# ESP8266_MySensorsGateway_v1_2.net
KiCad netlist of a schematic drawn in EAGLE
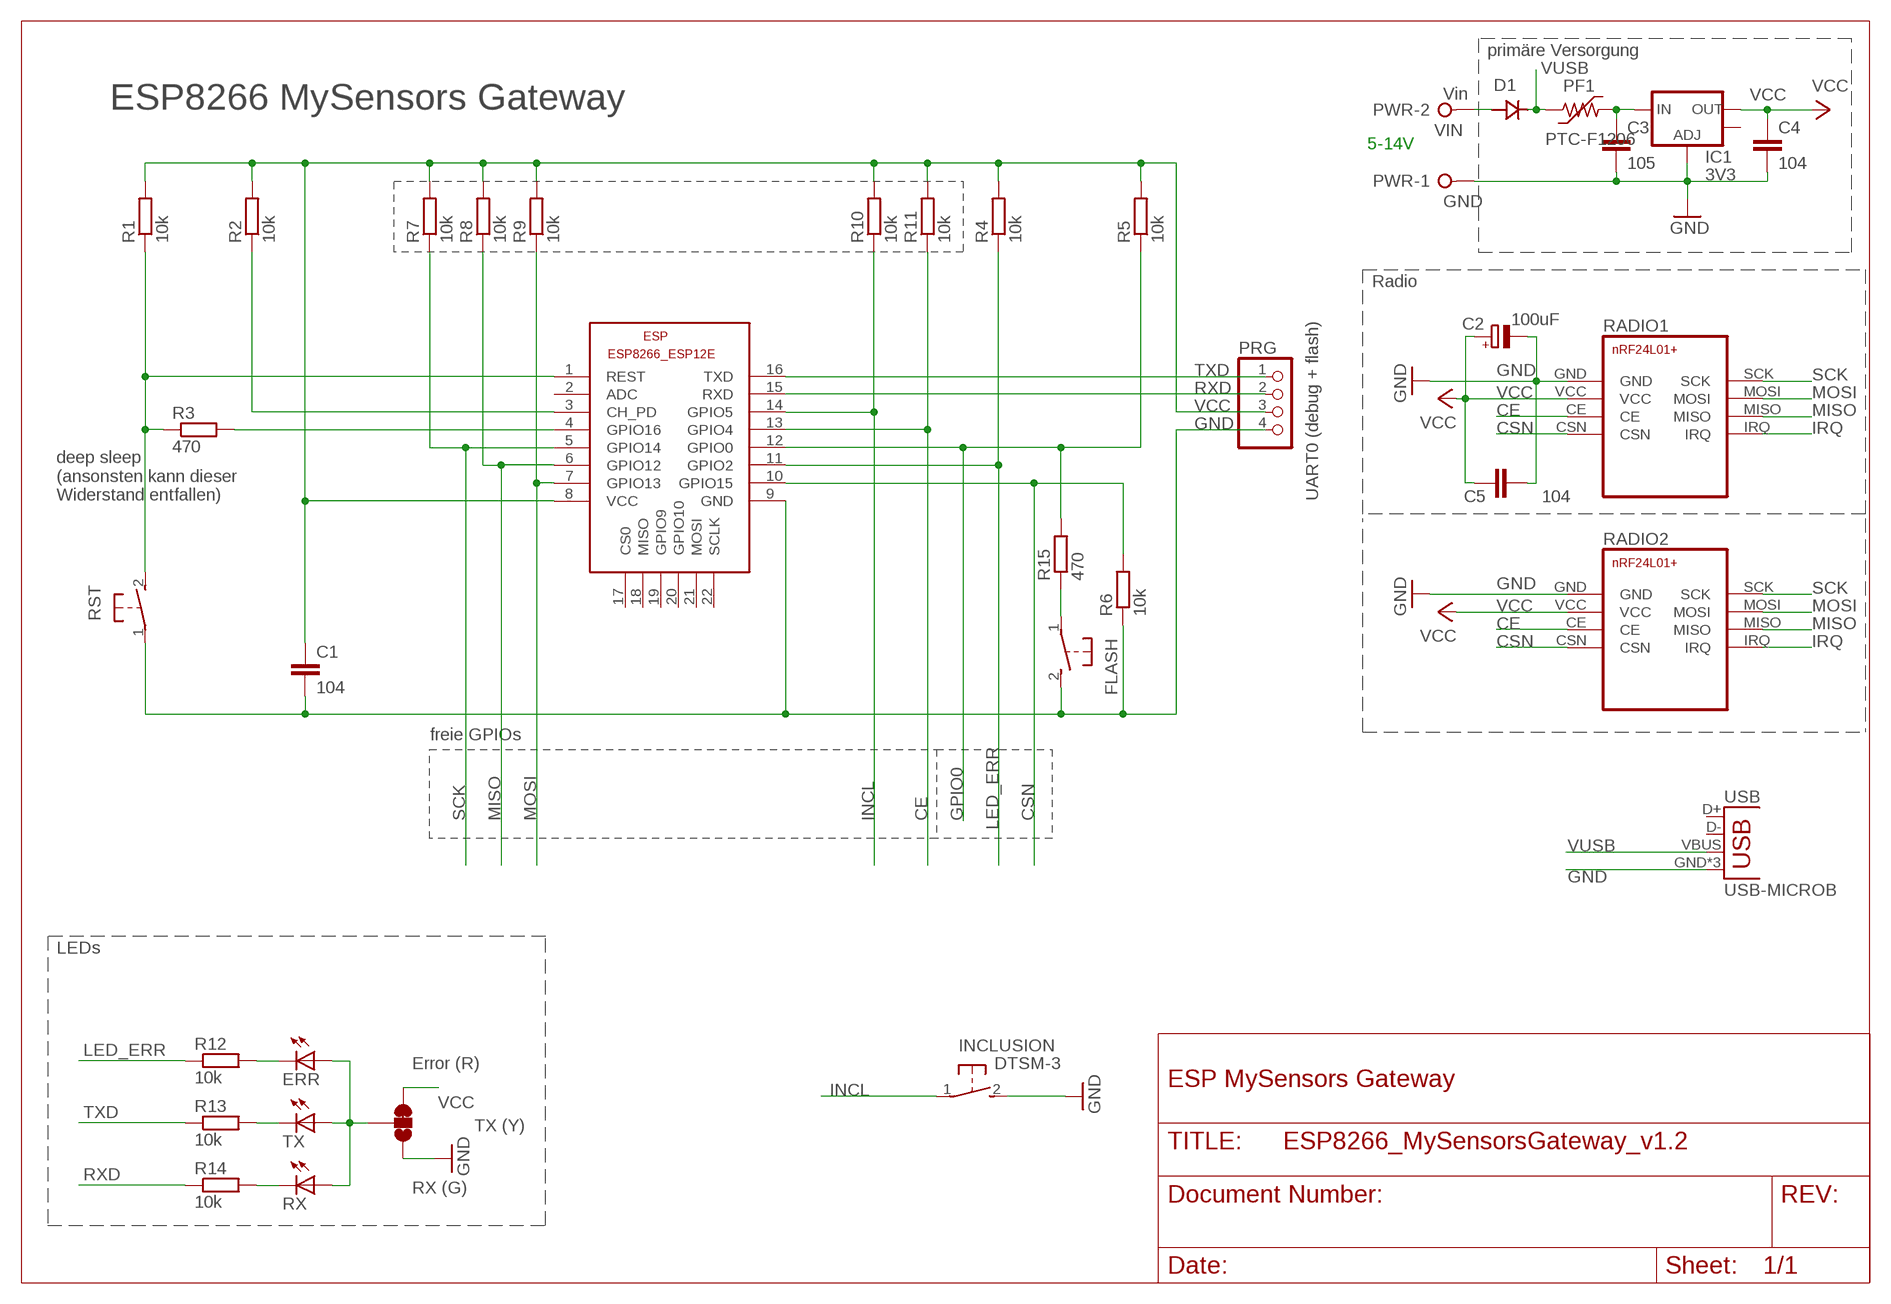
[diagram p0: schematic, sheet 1]

(export (version "E")
  (design (tool "Eeschema 10.0.6"))
  (components
    (comp (ref "C1")
      (value "104")
      (footprint "eagle-import:C0805")
      (libsource (lib "eagle-import") (part "C-EUC0805"))
    )
    (comp (ref "C2")
      (value "100uF")
      (footprint "eagle-import:E2,5-6E")
      (libsource (lib "eagle-import") (part "CPOL-EUE2,5-6E"))
    )
    (comp (ref "C3")
      (value "105")
      (footprint "eagle-import:C0805")
      (libsource (lib "eagle-import") (part "C-EUC0805"))
    )
    (comp (ref "C4")
      (value "104")
      (footprint "eagle-import:C0805")
      (libsource (lib "eagle-import") (part "C-EUC0805"))
    )
    (comp (ref "C5")
      (value "104")
      (footprint "eagle-import:C0805")
      (libsource (lib "eagle-import") (part "C-EUC0805"))
    )
    (comp (ref "D1")
      (value "SS14")
      (footprint "eagle-import:DO214")
      (libsource (lib "eagle-import") (part "SS14"))
    )
    (comp (ref "ERR")
      (value "R")
      (footprint "eagle-import:CHIPLED_1206")
      (libsource (lib "eagle-import") (part "LEDCHIPLED_1206"))
    )
    (comp (ref "ESP")
      (value "µC")
      (footprint "eagle-import:ESP8266-ESP12E")
      (libsource (lib "eagle-import") (part "ESP8266-12EESP8266-ESP12E"))
    )
    (comp (ref "FLASH")
      (value "DTSM-3")
      (footprint "eagle-import:DTSM-3")
      (libsource (lib "eagle-import") (part "DTSM-3"))
    )
    (comp (ref "IC1")
      (value "3V3")
      (footprint "eagle-import:SOT223")
      (libsource (lib "eagle-import") (part "V_REG_LM1117SOT223"))
    )
    (comp (ref "INCLUSION")
      (value "DTSM-3")
      (footprint "eagle-import:DTSM-3")
      (libsource (lib "eagle-import") (part "DTSM-3"))
    )
    (comp (ref "PF1")
      (value "PTC-F1206")
      (footprint "eagle-import:F1206")
      (libsource (lib "eagle-import") (part "PTC-F1206"))
    )
    (comp (ref "PRG")
      (value "PINHD-1X4_S")
      (footprint "eagle-import:1X04")
      (libsource (lib "eagle-import") (part "PINHD-1X4_S"))
    )
    (comp (ref "PWR")
      (value "Vin")
      (footprint "eagle-import:W237-132")
      (libsource (lib "eagle-import") (part "W237-02P"))
    )
    (comp (ref "R1")
      (value "10k")
      (footprint "eagle-import:R0805")
      (libsource (lib "eagle-import") (part "resistor_R-EU_R0805"))
    )
    (comp (ref "R2")
      (value "10k")
      (footprint "eagle-import:R0805")
      (libsource (lib "eagle-import") (part "resistor_R-EU_R0805"))
    )
    (comp (ref "R3")
      (value "470")
      (footprint "eagle-import:R0805")
      (libsource (lib "eagle-import") (part "resistor_R-EU_R0805"))
    )
    (comp (ref "R4")
      (value "10k")
      (footprint "eagle-import:R0805")
      (libsource (lib "eagle-import") (part "resistor_R-EU_R0805"))
    )
    (comp (ref "R5")
      (value "10k")
      (footprint "eagle-import:R0805")
      (libsource (lib "eagle-import") (part "resistor_R-EU_R0805"))
    )
    (comp (ref "R6")
      (value "10k")
      (footprint "eagle-import:R0805")
      (libsource (lib "eagle-import") (part "resistor_R-EU_R0805"))
    )
    (comp (ref "R7")
      (value "10k")
      (footprint "eagle-import:R0805")
      (libsource (lib "eagle-import") (part "resistor_R-EU_R0805"))
    )
    (comp (ref "R8")
      (value "10k")
      (footprint "eagle-import:R0805")
      (libsource (lib "eagle-import") (part "resistor_R-EU_R0805"))
    )
    (comp (ref "R9")
      (value "10k")
      (footprint "eagle-import:R0805")
      (libsource (lib "eagle-import") (part "resistor_R-EU_R0805"))
    )
    (comp (ref "R10")
      (value "10k")
      (footprint "eagle-import:R0805")
      (libsource (lib "eagle-import") (part "resistor_R-EU_R0805"))
    )
    (comp (ref "R11")
      (value "10k")
      (footprint "eagle-import:R0805")
      (libsource (lib "eagle-import") (part "resistor_R-EU_R0805"))
    )
    (comp (ref "R12")
      (value "10k")
      (footprint "eagle-import:R0805")
      (libsource (lib "eagle-import") (part "R-EU_R0805"))
    )
    (comp (ref "R13")
      (value "10k")
      (footprint "eagle-import:R0805")
      (libsource (lib "eagle-import") (part "R-EU_R0805"))
    )
    (comp (ref "R14")
      (value "10k")
      (footprint "eagle-import:R0805")
      (libsource (lib "eagle-import") (part "R-EU_R0805"))
    )
    (comp (ref "R15")
      (value "470")
      (footprint "eagle-import:R0805")
      (libsource (lib "eagle-import") (part "resistor_R-EU_R0805"))
    )
    (comp (ref "RADIO1")
      (value "NRF24L01+")
      (footprint "eagle-import:NRF24L01+")
      (libsource (lib "eagle-import") (part "NRF24L01+"))
    )
    (comp (ref "RADIO2")
      (value "NRF24L01+NRF24L01+MINI")
      (footprint "eagle-import:NRF24L01+MINI")
      (libsource (lib "eagle-import") (part "NRF24L01+NRF24L01+MINI"))
    )
    (comp (ref "RST")
      (value "DTSM-3")
      (footprint "eagle-import:DTSM-3")
      (libsource (lib "eagle-import") (part "DTSM-3"))
    )
    (comp (ref "RX")
      (value "G")
      (footprint "eagle-import:CHIPLED_1206")
      (libsource (lib "eagle-import") (part "LEDCHIPLED_1206"))
    )
    (comp (ref "SJ1")
      (value "JUMPER-PAD-3-2OF3_NC_BY_TRACE_SMALL")
      (footprint "eagle-import:PAD-JUMPER-3-2OF3_NC_BY_TRACE_YES_SILK_FULL_BOX")
      (libsource (lib "eagle-import") (part "JUMPER-PAD-3-2OF3_NC_BY_TRACE_SMALL"))
    )
    (comp (ref "TX")
      (value "Y")
      (footprint "eagle-import:CHIPLED_1206")
      (libsource (lib "eagle-import") (part "LEDCHIPLED_1206"))
    )
    (comp (ref "USB")
      (value "USB-MICROB")
      (footprint "eagle-import:USB-MICROB")
      (libsource (lib "eagle-import") (part "USB-MICROB"))
    )
  )
  (nets
    (net (code "1") (name "/CE") (class "Default")
      (node (ref "ESP") (pin "13") (pinfunction "GPIO4_13") (pintype "bidirectional"))
      (node (ref "R11") (pin "1") (pinfunction "1_1") (pintype "passive"))
      (node (ref "RADIO1") (pin "CE") (pinfunction "CE_CE") (pintype "bidirectional"))
      (node (ref "RADIO2") (pin "CE") (pinfunction "CE_CE") (pintype "bidirectional"))
    )
    (net (code "2") (name "/CSN") (class "Default")
      (node (ref "ESP") (pin "10") (pinfunction "GPIO15_10") (pintype "bidirectional"))
      (node (ref "R6") (pin "2") (pinfunction "2_2") (pintype "passive"))
      (node (ref "RADIO1") (pin "CSN") (pinfunction "CSN_CSN") (pintype "bidirectional"))
      (node (ref "RADIO2") (pin "CSN") (pinfunction "CSN_CSN") (pintype "bidirectional"))
    )
    (net (code "3") (name "/GPIO0") (class "Default")
      (node (ref "ESP") (pin "12") (pinfunction "GPIO0_12") (pintype "bidirectional"))
      (node (ref "R15") (pin "2") (pinfunction "2_2") (pintype "passive"))
      (node (ref "R5") (pin "1") (pinfunction "1_1") (pintype "passive"))
    )
    (net (code "4") (name "/INCL") (class "Default")
      (node (ref "ESP") (pin "14") (pinfunction "GPIO5_14") (pintype "bidirectional"))
      (node (ref "INCLUSION") (pin "1") (pinfunction "1_1") (pintype "passive"))
      (node (ref "R10") (pin "1") (pinfunction "1_1") (pintype "passive"))
    )
    (net (code "5") (name "/IRQ") (class "Default")
      (node (ref "RADIO1") (pin "IRQ") (pinfunction "IRQ_IRQ") (pintype "bidirectional"))
      (node (ref "RADIO2") (pin "IRQ") (pinfunction "IRQ_IRQ") (pintype "bidirectional"))
    )
    (net (code "6") (name "/LED_ERR") (class "Default")
      (node (ref "ESP") (pin "11") (pinfunction "GPIO2_11") (pintype "bidirectional"))
      (node (ref "R12") (pin "1") (pinfunction "1_1") (pintype "passive"))
      (node (ref "R4") (pin "1") (pinfunction "1_1") (pintype "passive"))
    )
    (net (code "7") (name "/MISO") (class "Default")
      (node (ref "ESP") (pin "6") (pinfunction "GPIO12_6") (pintype "bidirectional"))
      (node (ref "R8") (pin "1") (pinfunction "1_1") (pintype "passive"))
      (node (ref "RADIO1") (pin "MISO") (pinfunction "MISO_MISO") (pintype "bidirectional"))
      (node (ref "RADIO2") (pin "MISO") (pinfunction "MISO_MISO") (pintype "bidirectional"))
    )
    (net (code "8") (name "/MOSI") (class "Default")
      (node (ref "ESP") (pin "7") (pinfunction "GPIO13_7") (pintype "bidirectional"))
      (node (ref "R9") (pin "1") (pinfunction "1_1") (pintype "passive"))
      (node (ref "RADIO1") (pin "MOSI") (pinfunction "MOSI_MOSI") (pintype "bidirectional"))
      (node (ref "RADIO2") (pin "MOSI") (pinfunction "MOSI_MOSI") (pintype "bidirectional"))
    )
    (net (code "9") (name "/RXD") (class "Default")
      (node (ref "ESP") (pin "15") (pinfunction "RXD_15") (pintype "bidirectional"))
      (node (ref "PRG") (pin "2") (pinfunction "2_2") (pintype "passive"))
      (node (ref "R14") (pin "1") (pinfunction "1_1") (pintype "passive"))
    )
    (net (code "10") (name "/SCK") (class "Default")
      (node (ref "ESP") (pin "5") (pinfunction "GPIO14_5") (pintype "bidirectional"))
      (node (ref "R7") (pin "1") (pinfunction "1_1") (pintype "passive"))
      (node (ref "RADIO1") (pin "SCK") (pinfunction "SCK_SCK") (pintype "bidirectional"))
      (node (ref "RADIO2") (pin "SCK") (pinfunction "SCK_SCK") (pintype "bidirectional"))
    )
    (net (code "11") (name "/TXD") (class "Default")
      (node (ref "ESP") (pin "16") (pinfunction "TXD_16") (pintype "bidirectional"))
      (node (ref "PRG") (pin "1") (pinfunction "1_1") (pintype "passive"))
      (node (ref "R13") (pin "1") (pinfunction "1_1") (pintype "passive"))
    )
    (net (code "12") (name "/VIN") (class "Default")
      (node (ref "D1") (pin "ANODE") (pinfunction "ANODE_ANODE") (pintype "bidirectional"))
      (node (ref "PWR") (pin "2") (pinfunction "KL_2") (pintype "passive"))
    )
    (net (code "13") (name "/VUSB") (class "Default")
      (node (ref "D1") (pin "CATHODE") (pinfunction "CATHODE_CATHODE") (pintype "bidirectional"))
      (node (ref "PF1") (pin "1") (pinfunction "1_1") (pintype "passive"))
      (node (ref "USB") (pin "VBUS") (pinfunction "VBUS_VBUS") (pintype "bidirectional"))
    )
    (net (code "14") (name "GND") (class "Default")
      (node (ref "C1") (pin "2") (pinfunction "2_2") (pintype "passive"))
      (node (ref "C2") (pin "-") (pinfunction "-_-") (pintype "passive"))
      (node (ref "C3") (pin "2") (pinfunction "2_2") (pintype "passive"))
      (node (ref "C4") (pin "2") (pinfunction "2_2") (pintype "passive"))
      (node (ref "C5") (pin "2") (pinfunction "2_2") (pintype "passive"))
      (node (ref "ESP") (pin "9") (pinfunction "GND_9") (pintype "bidirectional"))
      (node (ref "FLASH") (pin "2") (pinfunction "2_2") (pintype "passive"))
      (node (ref "IC1") (pin "1") (pinfunction "ADJ_1") (pintype "input"))
      (node (ref "INCLUSION") (pin "2") (pinfunction "2_2") (pintype "passive"))
      (node (ref "PRG") (pin "4") (pinfunction "4_4") (pintype "passive"))
      (node (ref "PWR") (pin "1") (pinfunction "KL_1") (pintype "passive"))
      (node (ref "R6") (pin "1") (pinfunction "1_1") (pintype "passive"))
      (node (ref "RADIO1") (pin "GND") (pinfunction "GND_GND") (pintype "power_in"))
      (node (ref "RADIO2") (pin "GND") (pinfunction "GND_GND") (pintype "power_in"))
      (node (ref "RST") (pin "1") (pinfunction "1_1") (pintype "passive"))
      (node (ref "SJ1") (pin "1") (pinfunction "1_1") (pintype "passive"))
      (node (ref "USB") (pin "GND") (pinfunction "GND_GND") (pintype "bidirectional"))
      (node (ref "USB") (pin "MT1") (pinfunction "GND_MT1") (pintype "bidirectional"))
      (node (ref "USB") (pin "MT2") (pinfunction "GND_MT2") (pintype "bidirectional"))
    )
    (net (code "15") (name "Net-(ERR-PadA)") (class "Default")
      (node (ref "ERR") (pin "A") (pinfunction "A_A") (pintype "passive"))
      (node (ref "RX") (pin "A") (pinfunction "A_A") (pintype "passive"))
      (node (ref "SJ1") (pin "2") (pinfunction "2_2") (pintype "passive"))
      (node (ref "TX") (pin "A") (pinfunction "A_A") (pintype "passive"))
    )
    (net (code "16") (name "Net-(ERR-PadC)") (class "Default")
      (node (ref "ERR") (pin "C") (pinfunction "C_C") (pintype "passive"))
      (node (ref "R12") (pin "2") (pinfunction "2_2") (pintype "passive"))
    )
    (net (code "17") (name "Net-(ESP-CH_PD)") (class "Default")
      (node (ref "ESP") (pin "3") (pinfunction "CH_PD_3") (pintype "bidirectional"))
      (node (ref "R2") (pin "1") (pinfunction "1_1") (pintype "passive"))
    )
    (net (code "18") (name "Net-(ESP-GPIO16)") (class "Default")
      (node (ref "ESP") (pin "4") (pinfunction "GPIO16_4") (pintype "bidirectional"))
      (node (ref "R3") (pin "2") (pinfunction "2_2") (pintype "passive"))
    )
    (net (code "19") (name "Net-(ESP-REST)") (class "Default")
      (node (ref "ESP") (pin "1") (pinfunction "REST_1") (pintype "bidirectional"))
      (node (ref "R1") (pin "1") (pinfunction "1_1") (pintype "passive"))
      (node (ref "R3") (pin "1") (pinfunction "1_1") (pintype "passive"))
      (node (ref "RST") (pin "2") (pinfunction "2_2") (pintype "passive"))
    )
    (net (code "20") (name "Net-(FLASH-Pad1)") (class "Default")
      (node (ref "FLASH") (pin "1") (pinfunction "1_1") (pintype "passive"))
      (node (ref "R15") (pin "1") (pinfunction "1_1") (pintype "passive"))
    )
    (net (code "21") (name "Net-(IC1-IN)") (class "Default")
      (node (ref "C3") (pin "1") (pinfunction "1_1") (pintype "passive"))
      (node (ref "IC1") (pin "3") (pinfunction "IN_3") (pintype "input"))
      (node (ref "PF1") (pin "2") (pinfunction "2_2") (pintype "passive"))
    )
    (net (code "22") (name "Net-(R13-Pad2)") (class "Default")
      (node (ref "R13") (pin "2") (pinfunction "2_2") (pintype "passive"))
      (node (ref "TX") (pin "C") (pinfunction "C_C") (pintype "passive"))
    )
    (net (code "23") (name "Net-(R14-Pad2)") (class "Default")
      (node (ref "R14") (pin "2") (pinfunction "2_2") (pintype "passive"))
      (node (ref "RX") (pin "C") (pinfunction "C_C") (pintype "passive"))
    )
    (net (code "24") (name "VCC") (class "Default")
      (node (ref "C1") (pin "1") (pinfunction "1_1") (pintype "passive"))
      (node (ref "C2") (pin "+") (pinfunction "+_+") (pintype "passive"))
      (node (ref "C4") (pin "1") (pinfunction "1_1") (pintype "passive"))
      (node (ref "C5") (pin "1") (pinfunction "1_1") (pintype "passive"))
      (node (ref "ESP") (pin "8") (pinfunction "VCC_8") (pintype "bidirectional"))
      (node (ref "IC1") (pin "2") (pinfunction "OUT_2") (pintype "output"))
      (node (ref "PRG") (pin "3") (pinfunction "3_3") (pintype "passive"))
      (node (ref "R1") (pin "2") (pinfunction "2_2") (pintype "passive"))
      (node (ref "R10") (pin "2") (pinfunction "2_2") (pintype "passive"))
      (node (ref "R11") (pin "2") (pinfunction "2_2") (pintype "passive"))
      (node (ref "R2") (pin "2") (pinfunction "2_2") (pintype "passive"))
      (node (ref "R4") (pin "2") (pinfunction "2_2") (pintype "passive"))
      (node (ref "R5") (pin "2") (pinfunction "2_2") (pintype "passive"))
      (node (ref "R7") (pin "2") (pinfunction "2_2") (pintype "passive"))
      (node (ref "R8") (pin "2") (pinfunction "2_2") (pintype "passive"))
      (node (ref "R9") (pin "2") (pinfunction "2_2") (pintype "passive"))
      (node (ref "RADIO1") (pin "VCC") (pinfunction "VCC_VCC") (pintype "power_in"))
      (node (ref "RADIO2") (pin "VCC") (pinfunction "VCC_VCC") (pintype "power_in"))
      (node (ref "SJ1") (pin "3") (pinfunction "3_3") (pintype "passive"))
    )
    (net (code "25") (name "unconnected-(ESP-ADC-Pad2)") (class "Default")
      (node (ref "ESP") (pin "2") (pinfunction "ADC_2") (pintype "bidirectional"))
    )
    (net (code "26") (name "unconnected-(ESP-CS0-Pad17)") (class "Default")
      (node (ref "ESP") (pin "17") (pinfunction "CS0_17") (pintype "bidirectional"))
    )
    (net (code "27") (name "unconnected-(ESP-GPIO9-Pad19)") (class "Default")
      (node (ref "ESP") (pin "19") (pinfunction "GPIO9_19") (pintype "bidirectional"))
    )
    (net (code "28") (name "unconnected-(ESP-GPIO10-Pad20)") (class "Default")
      (node (ref "ESP") (pin "20") (pinfunction "GPIO10_20") (pintype "bidirectional"))
    )
    (net (code "29") (name "unconnected-(ESP-MISO-Pad18)") (class "Default")
      (node (ref "ESP") (pin "18") (pinfunction "MISO_18") (pintype "bidirectional"))
    )
    (net (code "30") (name "unconnected-(ESP-MOSI-Pad21)") (class "Default")
      (node (ref "ESP") (pin "21") (pinfunction "MOSI_21") (pintype "bidirectional"))
    )
    (net (code "31") (name "unconnected-(ESP-SCLK-Pad22)") (class "Default")
      (node (ref "ESP") (pin "22") (pinfunction "SCLK_22") (pintype "bidirectional"))
    )
    (net (code "32") (name "unconnected-(IC1-OUT-Pad4)") (class "Default")
      (node (ref "IC1") (pin "4") (pinfunction "OUT_4") (pintype "output"))
    )
    (net (code "33") (name "unconnected-(USB-PadD+)") (class "Default")
      (node (ref "USB") (pin "D+") (pinfunction "D+_D+") (pintype "bidirectional"))
    )
    (net (code "34") (name "unconnected-(USB-PadD-)") (class "Default")
      (node (ref "USB") (pin "D-") (pinfunction "D-_D-") (pintype "bidirectional"))
    )
  )
)
